# VCO.net
KiCad netlist of a schematic drawn in EAGLE
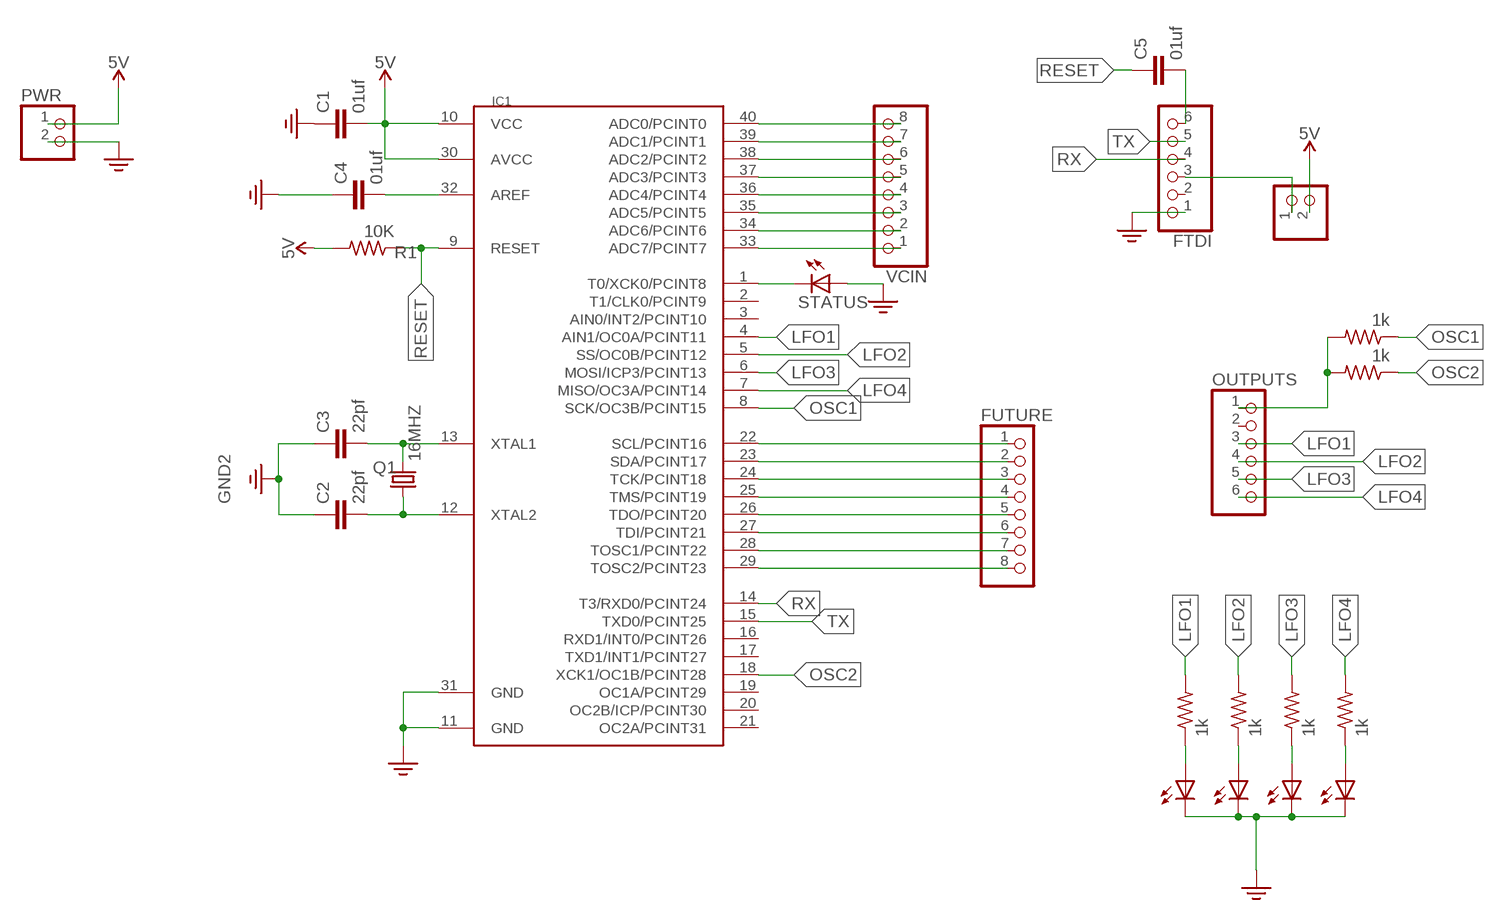
[diagram p0: schematic, sheet 1]

(export (version "E")
  (design (tool "Eeschema 10.0.6"))
  (components
    (comp (ref "C1")
      (value "01uf")
      (footprint "eagle-import:C025-024X044")
      (libsource (lib "eagle-import") (part "C-EU025-024X044"))
    )
    (comp (ref "C2")
      (value "22pf")
      (footprint "eagle-import:C025-024X044")
      (libsource (lib "eagle-import") (part "C-EU025-024X044"))
    )
    (comp (ref "C3")
      (value "22pf")
      (footprint "eagle-import:C025-024X044")
      (libsource (lib "eagle-import") (part "C-EU025-024X044"))
    )
    (comp (ref "C4")
      (value "01uf")
      (footprint "eagle-import:C025-024X044")
      (libsource (lib "eagle-import") (part "C-EU025-024X044"))
    )
    (comp (ref "C5")
      (value "01uf")
      (footprint "eagle-import:C025-024X044")
      (libsource (lib "eagle-import") (part "C-EU025-024X044"))
    )
    (comp (ref "FTDI")
      (value "PINHD-1X6")
      (footprint "eagle-import:1X06")
      (libsource (lib "eagle-import") (part "pinhead_325_PINHD-1X6"))
    )
    (comp (ref "FUTURE")
      (value "PINHD-1X8BIG")
      (footprint "eagle-import:1X08-BIG")
      (libsource (lib "eagle-import") (part "PINHD-1X8BIG"))
    )
    (comp (ref "IC1")
      (value "MEGA1284P")
      (footprint "eagle-import:DIL40")
      (libsource (lib "eagle-import") (part "MEGA1284P"))
    )
    (comp (ref "LFO1")
      (value "LED5MM")
      (footprint "eagle-import:LED5MM")
      (libsource (lib "eagle-import") (part "LED5MM"))
    )
    (comp (ref "LFO2")
      (value "LED5MM")
      (footprint "eagle-import:LED5MM")
      (libsource (lib "eagle-import") (part "LED5MM"))
    )
    (comp (ref "LFO3")
      (value "LED5MM")
      (footprint "eagle-import:LED5MM")
      (libsource (lib "eagle-import") (part "LED5MM"))
    )
    (comp (ref "LFO4")
      (value "LED5MM")
      (footprint "eagle-import:LED5MM")
      (libsource (lib "eagle-import") (part "LED5MM"))
    )
    (comp (ref "OUTPUTS")
      (value "PINHD-1X6")
      (footprint "eagle-import:1X06")
      (libsource (lib "eagle-import") (part "PINHD-1X6"))
    )
    (comp (ref "PWR")
      (value "PINHD-1X2")
      (footprint "eagle-import:1X02")
      (libsource (lib "eagle-import") (part "PINHD-1X2"))
    )
    (comp (ref "PWR1")
      (value "PINHD-1X2")
      (footprint "eagle-import:1X02")
      (libsource (lib "eagle-import") (part "PINHD-1X2"))
    )
    (comp (ref "Q1")
      (value "16MHZ")
      (footprint "eagle-import:HC49_S")
      (libsource (lib "eagle-import") (part "CRYSTALHC49S"))
    )
    (comp (ref "R1")
      (value "10K")
      (footprint "eagle-import:0207_12")
      (libsource (lib "eagle-import") (part "R-US_0207/12"))
    )
    (comp (ref "R2")
      (value "1k")
      (footprint "eagle-import:0207_12")
      (libsource (lib "eagle-import") (part "R-US_0207/12"))
    )
    (comp (ref "R3")
      (value "1k")
      (footprint "eagle-import:0207_12")
      (libsource (lib "eagle-import") (part "R-US_0207/12"))
    )
    (comp (ref "R4")
      (value "1k")
      (footprint "eagle-import:0207_12")
      (libsource (lib "eagle-import") (part "R-US_0207/12"))
    )
    (comp (ref "R5")
      (value "1k")
      (footprint "eagle-import:0207_12")
      (libsource (lib "eagle-import") (part "R-US_0207/12"))
    )
    (comp (ref "R6")
      (value "1k")
      (footprint "eagle-import:0207_12")
      (libsource (lib "eagle-import") (part "R-US_0207/12"))
    )
    (comp (ref "R7")
      (value "1k")
      (footprint "eagle-import:0207_12")
      (libsource (lib "eagle-import") (part "R-US_0207/12"))
    )
    (comp (ref "STATUS")
      (value "LED5MM")
      (footprint "eagle-import:LED5MM")
      (libsource (lib "eagle-import") (part "LED5MM"))
    )
    (comp (ref "VCIN")
      (value "PINHD-1X8")
      (footprint "eagle-import:1X08")
      (libsource (lib "eagle-import") (part "PINHD-1X8"))
    )
  )
  (nets
    (net (code "1") (name "5V") (class "Default")
      (node (ref "C1") (pin "2") (pinfunction "2_2") (pintype "passive"))
      (node (ref "IC1") (pin "10") (pinfunction "VCC_10") (pintype "bidirectional"))
      (node (ref "IC1") (pin "30") (pinfunction "AVCC_30") (pintype "bidirectional"))
      (node (ref "PWR") (pin "1") (pinfunction "1_1") (pintype "passive"))
      (node (ref "PWR1") (pin "2") (pinfunction "2_2") (pintype "passive"))
      (node (ref "R1") (pin "2") (pinfunction "2_2") (pintype "passive"))
    )
    (net (code "2") (name "GND2") (class "Default")
      (node (ref "C1") (pin "1") (pinfunction "1_1") (pintype "passive"))
      (node (ref "C2") (pin "1") (pinfunction "1_1") (pintype "passive"))
      (node (ref "C3") (pin "1") (pinfunction "1_1") (pintype "passive"))
      (node (ref "C4") (pin "1") (pinfunction "1_1") (pintype "passive"))
      (node (ref "FTDI") (pin "1") (pinfunction "1_1") (pintype "passive"))
      (node (ref "IC1") (pin "11") (pinfunction "GND_11") (pintype "bidirectional"))
      (node (ref "IC1") (pin "31") (pinfunction "GND_31") (pintype "bidirectional"))
      (node (ref "LFO1") (pin "K") (pinfunction "C_K") (pintype "passive"))
      (node (ref "LFO2") (pin "K") (pinfunction "C_K") (pintype "passive"))
      (node (ref "LFO3") (pin "K") (pinfunction "C_K") (pintype "passive"))
      (node (ref "LFO4") (pin "K") (pinfunction "C_K") (pintype "passive"))
      (node (ref "PWR") (pin "2") (pinfunction "2_2") (pintype "passive"))
      (node (ref "STATUS") (pin "A") (pinfunction "A_A") (pintype "passive"))
    )
    (net (code "3") (name "LFO1") (class "Default")
      (node (ref "IC1") (pin "4") (pinfunction "AIN1/OC0A/PCINT11_4") (pintype "bidirectional"))
      (node (ref "OUTPUTS") (pin "3") (pinfunction "3_3") (pintype "passive"))
      (node (ref "R4") (pin "2") (pinfunction "2_2") (pintype "passive"))
    )
    (net (code "4") (name "LFO2") (class "Default")
      (node (ref "IC1") (pin "5") (pinfunction "SS/OC0B/PCINT12_5") (pintype "bidirectional"))
      (node (ref "OUTPUTS") (pin "4") (pinfunction "4_4") (pintype "passive"))
      (node (ref "R3") (pin "2") (pinfunction "2_2") (pintype "passive"))
    )
    (net (code "5") (name "LFO3") (class "Default")
      (node (ref "IC1") (pin "6") (pinfunction "MOSI/ICP3/PCINT13_6") (pintype "bidirectional"))
      (node (ref "OUTPUTS") (pin "5") (pinfunction "5_5") (pintype "passive"))
      (node (ref "R2") (pin "2") (pinfunction "2_2") (pintype "passive"))
    )
    (net (code "6") (name "LFO4") (class "Default")
      (node (ref "IC1") (pin "7") (pinfunction "MISO/OC3A/PCINT14_7") (pintype "bidirectional"))
      (node (ref "OUTPUTS") (pin "6") (pinfunction "6_6") (pintype "passive"))
      (node (ref "R5") (pin "2") (pinfunction "2_2") (pintype "passive"))
    )
    (net (code "7") (name "Net-(C5-Pad2)") (class "Default")
      (node (ref "C5") (pin "2") (pinfunction "2_2") (pintype "passive"))
      (node (ref "FTDI") (pin "6") (pinfunction "6_6") (pintype "passive"))
    )
    (net (code "8") (name "Net-(FTDI-Pad3)") (class "Default")
      (node (ref "FTDI") (pin "3") (pinfunction "3_3") (pintype "passive"))
      (node (ref "PWR1") (pin "1") (pinfunction "1_1") (pintype "passive"))
    )
    (net (code "9") (name "Net-(IC1-ADC0{slash}PCINT0)") (class "Default")
      (node (ref "IC1") (pin "40") (pinfunction "ADC0/PCINT0_40") (pintype "bidirectional"))
      (node (ref "VCIN") (pin "8") (pinfunction "8_8") (pintype "passive"))
    )
    (net (code "10") (name "Net-(IC1-ADC1{slash}PCINT1)") (class "Default")
      (node (ref "IC1") (pin "39") (pinfunction "ADC1/PCINT1_39") (pintype "bidirectional"))
      (node (ref "VCIN") (pin "7") (pinfunction "7_7") (pintype "passive"))
    )
    (net (code "11") (name "Net-(IC1-ADC2{slash}PCINT2)") (class "Default")
      (node (ref "IC1") (pin "38") (pinfunction "ADC2/PCINT2_38") (pintype "bidirectional"))
      (node (ref "VCIN") (pin "6") (pinfunction "6_6") (pintype "passive"))
    )
    (net (code "12") (name "Net-(IC1-ADC3{slash}PCINT3)") (class "Default")
      (node (ref "IC1") (pin "37") (pinfunction "ADC3/PCINT3_37") (pintype "bidirectional"))
      (node (ref "VCIN") (pin "5") (pinfunction "5_5") (pintype "passive"))
    )
    (net (code "13") (name "Net-(IC1-ADC4{slash}PCINT4)") (class "Default")
      (node (ref "IC1") (pin "36") (pinfunction "ADC4/PCINT4_36") (pintype "bidirectional"))
      (node (ref "VCIN") (pin "4") (pinfunction "4_4") (pintype "passive"))
    )
    (net (code "14") (name "Net-(IC1-ADC5{slash}PCINT5)") (class "Default")
      (node (ref "IC1") (pin "35") (pinfunction "ADC5/PCINT5_35") (pintype "bidirectional"))
      (node (ref "VCIN") (pin "3") (pinfunction "3_3") (pintype "passive"))
    )
    (net (code "15") (name "Net-(IC1-ADC6{slash}PCINT6)") (class "Default")
      (node (ref "IC1") (pin "34") (pinfunction "ADC6/PCINT6_34") (pintype "bidirectional"))
      (node (ref "VCIN") (pin "2") (pinfunction "2_2") (pintype "passive"))
    )
    (net (code "16") (name "Net-(IC1-ADC7{slash}PCINT7)") (class "Default")
      (node (ref "IC1") (pin "33") (pinfunction "ADC7/PCINT7_33") (pintype "bidirectional"))
      (node (ref "VCIN") (pin "1") (pinfunction "1_1") (pintype "passive"))
    )
    (net (code "17") (name "Net-(IC1-AREF)") (class "Default")
      (node (ref "C4") (pin "2") (pinfunction "2_2") (pintype "passive"))
      (node (ref "IC1") (pin "32") (pinfunction "AREF_32") (pintype "bidirectional"))
    )
    (net (code "18") (name "Net-(IC1-SCL{slash}PCINT16)") (class "Default")
      (node (ref "FUTURE") (pin "1") (pinfunction "1_1") (pintype "passive"))
      (node (ref "IC1") (pin "22") (pinfunction "SCL/PCINT16_22") (pintype "bidirectional"))
    )
    (net (code "19") (name "Net-(IC1-SDA{slash}PCINT17)") (class "Default")
      (node (ref "FUTURE") (pin "2") (pinfunction "2_2") (pintype "passive"))
      (node (ref "IC1") (pin "23") (pinfunction "SDA/PCINT17_23") (pintype "bidirectional"))
    )
    (net (code "20") (name "Net-(IC1-T0{slash}XCK0{slash}PCINT8)") (class "Default")
      (node (ref "IC1") (pin "1") (pinfunction "T0/XCK0/PCINT8_1") (pintype "bidirectional"))
      (node (ref "STATUS") (pin "K") (pinfunction "C_K") (pintype "passive"))
    )
    (net (code "21") (name "Net-(IC1-TCK{slash}PCINT18)") (class "Default")
      (node (ref "FUTURE") (pin "3") (pinfunction "3_3") (pintype "passive"))
      (node (ref "IC1") (pin "24") (pinfunction "TCK/PCINT18_24") (pintype "bidirectional"))
    )
    (net (code "22") (name "Net-(IC1-TDI{slash}PCINT21)") (class "Default")
      (node (ref "FUTURE") (pin "6") (pinfunction "6_6") (pintype "passive"))
      (node (ref "IC1") (pin "27") (pinfunction "TDI/PCINT21_27") (pintype "bidirectional"))
    )
    (net (code "23") (name "Net-(IC1-TDO{slash}PCINT20)") (class "Default")
      (node (ref "FUTURE") (pin "5") (pinfunction "5_5") (pintype "passive"))
      (node (ref "IC1") (pin "26") (pinfunction "TDO/PCINT20_26") (pintype "bidirectional"))
    )
    (net (code "24") (name "Net-(IC1-TMS{slash}PCINT19)") (class "Default")
      (node (ref "FUTURE") (pin "4") (pinfunction "4_4") (pintype "passive"))
      (node (ref "IC1") (pin "25") (pinfunction "TMS/PCINT19_25") (pintype "bidirectional"))
    )
    (net (code "25") (name "Net-(IC1-TOSC1{slash}PCINT22)") (class "Default")
      (node (ref "FUTURE") (pin "7") (pinfunction "7_7") (pintype "passive"))
      (node (ref "IC1") (pin "28") (pinfunction "TOSC1/PCINT22_28") (pintype "bidirectional"))
    )
    (net (code "26") (name "Net-(IC1-TOSC2{slash}PCINT23)") (class "Default")
      (node (ref "FUTURE") (pin "8") (pinfunction "8_8") (pintype "passive"))
      (node (ref "IC1") (pin "29") (pinfunction "TOSC2/PCINT23_29") (pintype "bidirectional"))
    )
    (net (code "27") (name "Net-(IC1-XTAL1)") (class "Default")
      (node (ref "C3") (pin "2") (pinfunction "2_2") (pintype "passive"))
      (node (ref "IC1") (pin "13") (pinfunction "XTAL1_13") (pintype "bidirectional"))
      (node (ref "Q1") (pin "2") (pinfunction "2_2") (pintype "passive"))
    )
    (net (code "28") (name "Net-(IC1-XTAL2)") (class "Default")
      (node (ref "C2") (pin "2") (pinfunction "2_2") (pintype "passive"))
      (node (ref "IC1") (pin "12") (pinfunction "XTAL2_12") (pintype "bidirectional"))
      (node (ref "Q1") (pin "1") (pinfunction "1_1") (pintype "passive"))
    )
    (net (code "29") (name "Net-(LFO1-PadA)") (class "Default")
      (node (ref "LFO1") (pin "A") (pinfunction "A_A") (pintype "passive"))
      (node (ref "R4") (pin "1") (pinfunction "1_1") (pintype "passive"))
    )
    (net (code "30") (name "Net-(LFO2-PadA)") (class "Default")
      (node (ref "LFO2") (pin "A") (pinfunction "A_A") (pintype "passive"))
      (node (ref "R3") (pin "1") (pinfunction "1_1") (pintype "passive"))
    )
    (net (code "31") (name "Net-(LFO3-PadA)") (class "Default")
      (node (ref "LFO3") (pin "A") (pinfunction "A_A") (pintype "passive"))
      (node (ref "R2") (pin "1") (pinfunction "1_1") (pintype "passive"))
    )
    (net (code "32") (name "Net-(LFO4-PadA)") (class "Default")
      (node (ref "LFO4") (pin "A") (pinfunction "A_A") (pintype "passive"))
      (node (ref "R5") (pin "1") (pinfunction "1_1") (pintype "passive"))
    )
    (net (code "33") (name "Net-(OUTPUTS-Pad1)") (class "Default")
      (node (ref "OUTPUTS") (pin "1") (pinfunction "1_1") (pintype "passive"))
      (node (ref "R6") (pin "2") (pinfunction "2_2") (pintype "passive"))
      (node (ref "R7") (pin "2") (pinfunction "2_2") (pintype "passive"))
    )
    (net (code "34") (name "OSC1") (class "Default")
      (node (ref "IC1") (pin "8") (pinfunction "SCK/OC3B/PCINT15_8") (pintype "bidirectional"))
      (node (ref "R6") (pin "1") (pinfunction "1_1") (pintype "passive"))
    )
    (net (code "35") (name "OSC2") (class "Default")
      (node (ref "IC1") (pin "18") (pinfunction "XCK1/OC1B/PCINT28_18") (pintype "bidirectional"))
      (node (ref "R7") (pin "1") (pinfunction "1_1") (pintype "passive"))
    )
    (net (code "36") (name "RESET") (class "Default")
      (node (ref "C5") (pin "1") (pinfunction "1_1") (pintype "passive"))
      (node (ref "IC1") (pin "9") (pinfunction "RESET_9") (pintype "bidirectional"))
      (node (ref "R1") (pin "1") (pinfunction "1_1") (pintype "passive"))
    )
    (net (code "37") (name "RX") (class "Default")
      (node (ref "FTDI") (pin "4") (pinfunction "4_4") (pintype "passive"))
      (node (ref "IC1") (pin "14") (pinfunction "T3/RXD0/PCINT24_14") (pintype "bidirectional"))
    )
    (net (code "38") (name "TX") (class "Default")
      (node (ref "FTDI") (pin "5") (pinfunction "5_5") (pintype "passive"))
      (node (ref "IC1") (pin "15") (pinfunction "TXD0/PCINT25_15") (pintype "bidirectional"))
    )
    (net (code "39") (name "unconnected-(FTDI-Pad2)") (class "Default")
      (node (ref "FTDI") (pin "2") (pinfunction "2_2") (pintype "passive"))
    )
    (net (code "40") (name "unconnected-(IC1-AIN0{slash}INT2{slash}PCINT10-Pad3)") (class "Default")
      (node (ref "IC1") (pin "3") (pinfunction "AIN0/INT2/PCINT10_3") (pintype "bidirectional"))
    )
    (net (code "41") (name "unconnected-(IC1-OC1A{slash}PCINT29-Pad19)") (class "Default")
      (node (ref "IC1") (pin "19") (pinfunction "OC1A/PCINT29_19") (pintype "bidirectional"))
    )
    (net (code "42") (name "unconnected-(IC1-OC2A{slash}PCINT31-Pad21)") (class "Default")
      (node (ref "IC1") (pin "21") (pinfunction "OC2A/PCINT31_21") (pintype "bidirectional"))
    )
    (net (code "43") (name "unconnected-(IC1-OC2B{slash}ICP{slash}PCINT30-Pad20)") (class "Default")
      (node (ref "IC1") (pin "20") (pinfunction "OC2B/ICP/PCINT30_20") (pintype "bidirectional"))
    )
    (net (code "44") (name "unconnected-(IC1-RXD1{slash}INT0{slash}PCINT26-Pad16)") (class "Default")
      (node (ref "IC1") (pin "16") (pinfunction "RXD1/INT0/PCINT26_16") (pintype "bidirectional"))
    )
    (net (code "45") (name "unconnected-(IC1-T1{slash}CLK0{slash}PCINT9-Pad2)") (class "Default")
      (node (ref "IC1") (pin "2") (pinfunction "T1/CLK0/PCINT9_2") (pintype "bidirectional"))
    )
    (net (code "46") (name "unconnected-(IC1-TXD1{slash}INT1{slash}PCINT27-Pad17)") (class "Default")
      (node (ref "IC1") (pin "17") (pinfunction "TXD1/INT1/PCINT27_17") (pintype "bidirectional"))
    )
    (net (code "47") (name "unconnected-(OUTPUTS-Pad2)") (class "Default")
      (node (ref "OUTPUTS") (pin "2") (pinfunction "2_2") (pintype "passive"))
    )
  )
)
